# ProPrj___2025-03-14.net
KiCad netlist of a schematic drawn in EasyEDA Pro
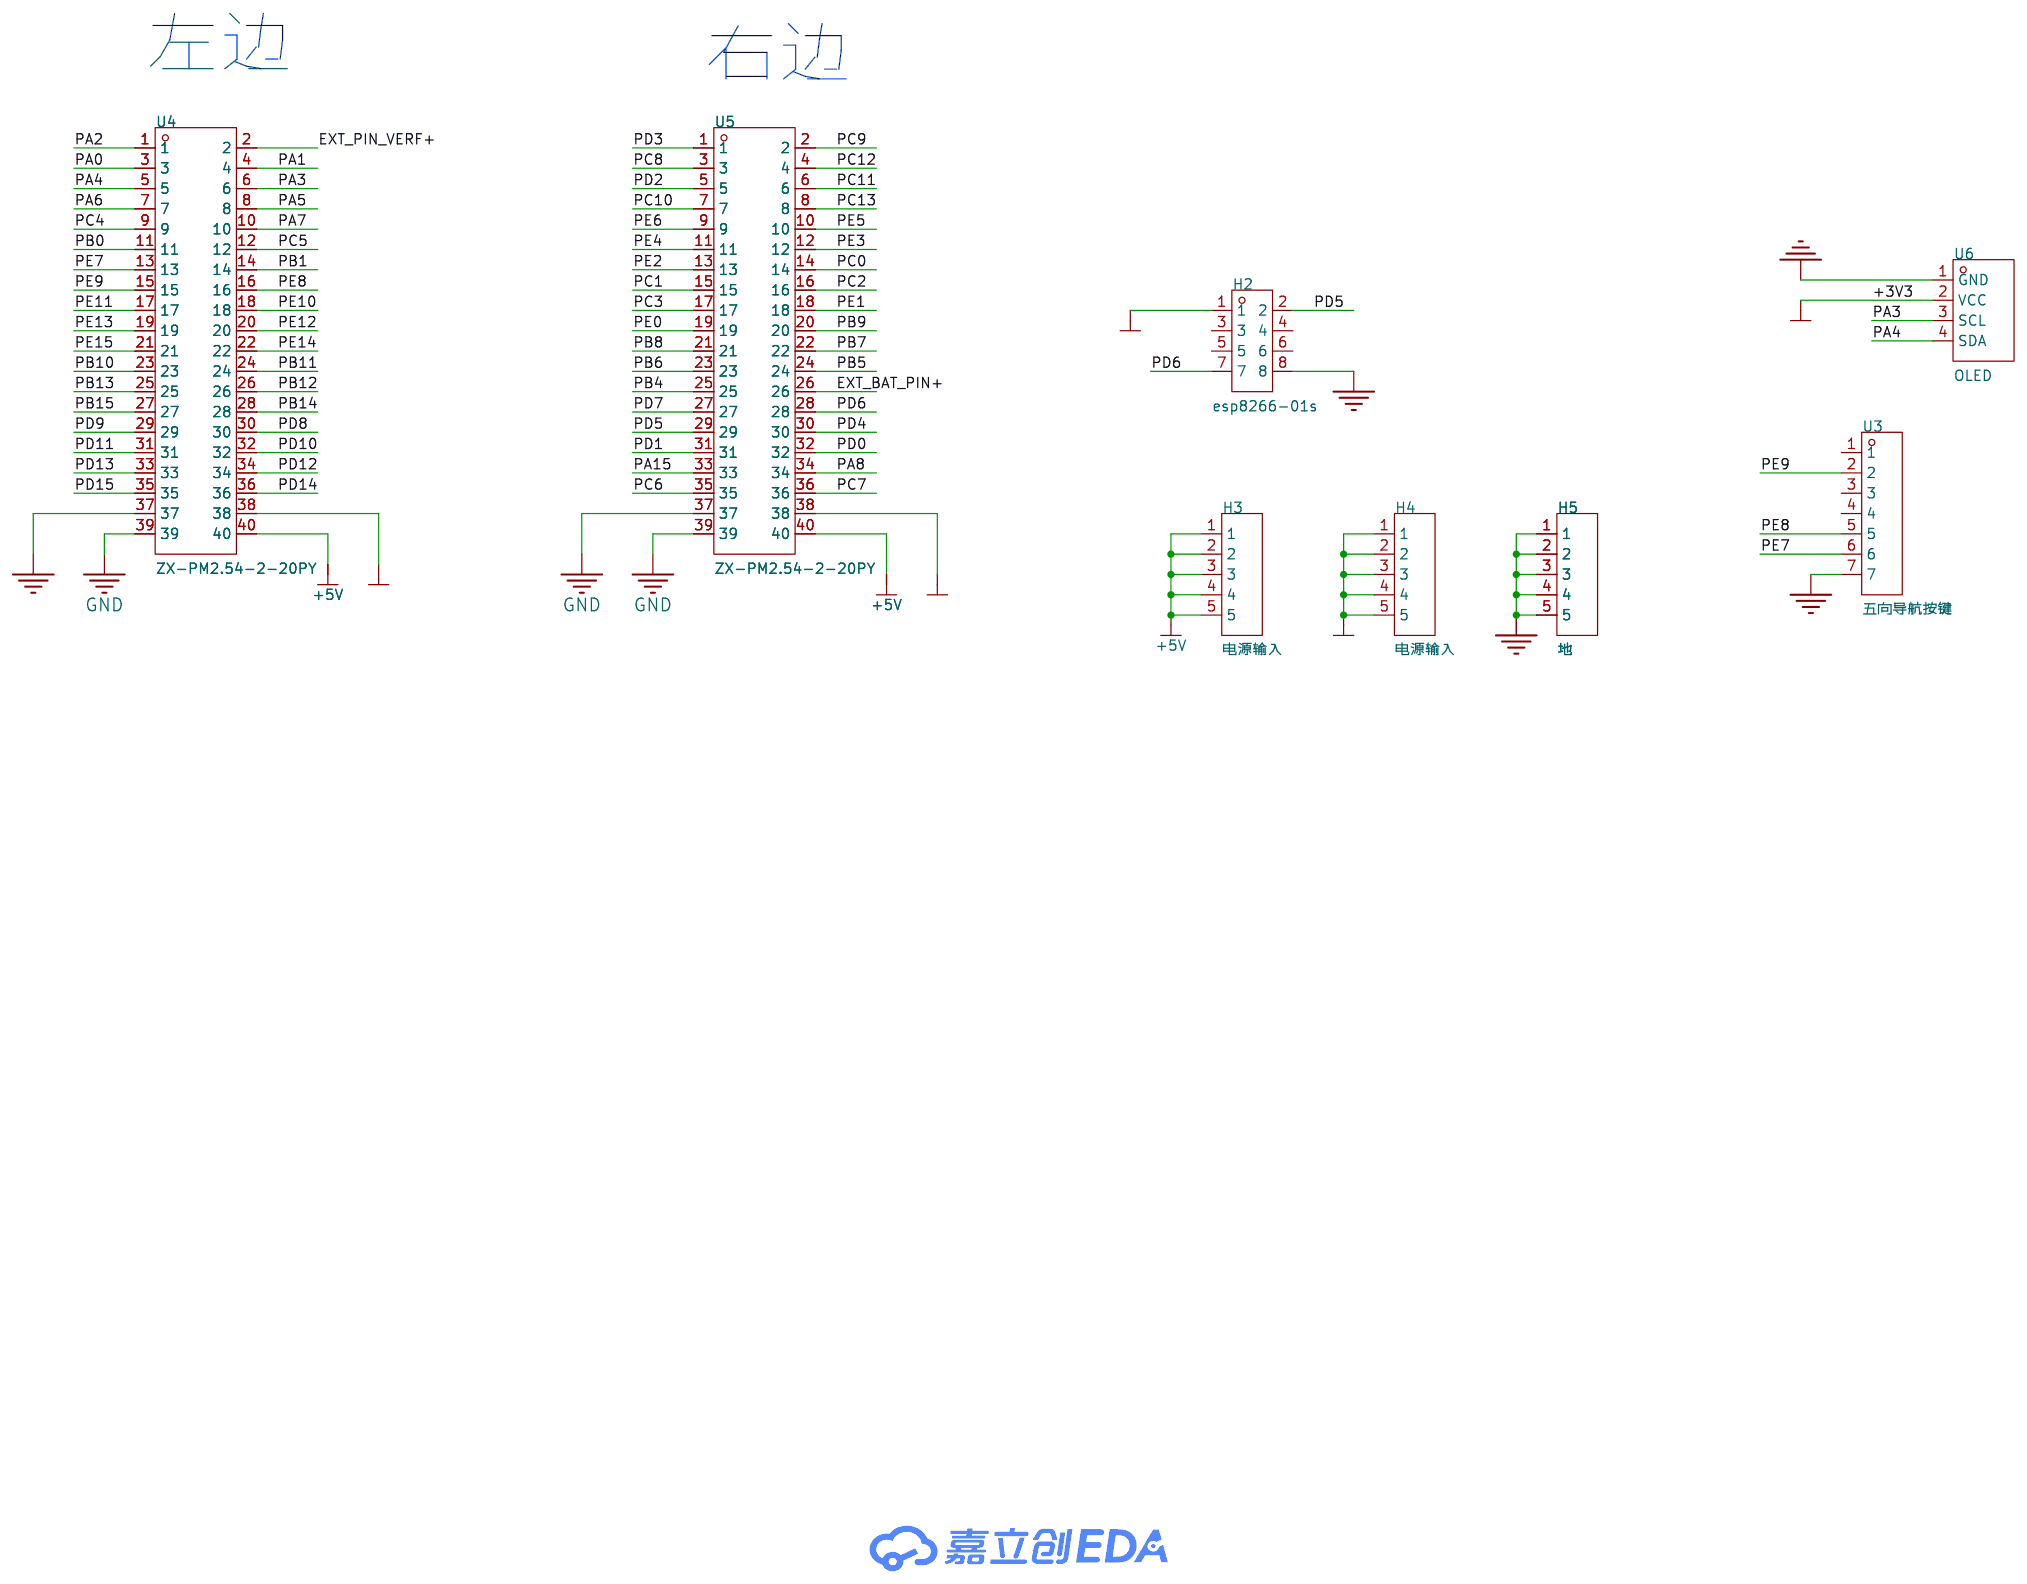
[diagram p0: schematic sheet]

(export (version "E")
  (design (tool "Eeschema 10.0.6"))
  (components
    (comp (ref "H2")
      (value "esp8266-01s")
      (footprint "easyedapro:HDR-TH_8P-P2.54-V-F-R2-C4-S2.54")
      (fields (field (name "Manufacturer Part") "PM254V-12-08-H85") (field (name "Manufacturer") "XFCN(兴飞)"))
      (libsource (lib "easyedapro") (part "PM254V-12-08-H85_C2834799"))
    )
    (comp (ref "H3")
      (value "电源输入")
      (footprint "easyedapro:HDR-TH_5P-P2.54-V-M")
      (fields (field (name "Manufacturer Part") "PZ254V-11-05P") (field (name "Manufacturer") "XFCN(兴飞)"))
      (libsource (lib "easyedapro") (part "PZ254V-11-05P"))
    )
    (comp (ref "H4")
      (value "电源输入")
      (footprint "easyedapro:HDR-TH_5P-P2.54-V-M")
      (fields (field (name "Manufacturer Part") "PZ254V-11-05P") (field (name "Manufacturer") "XFCN(兴飞)"))
      (libsource (lib "easyedapro") (part "PZ254V-11-05P"))
    )
    (comp (ref "H5")
      (value "地")
      (footprint "easyedapro:HDR-TH_5P-P2.54-V-M")
      (fields (field (name "Manufacturer Part") "PZ254V-11-05P") (field (name "Manufacturer") "XFCN(兴飞)"))
      (libsource (lib "easyedapro") (part "PZ254V-11-05P"))
    )
    (comp (ref "U3")
      (value "五向导航按键")
      (footprint "easyedapro:HDR-TH_7P-P2.54-H-F-W10.0-N")
      (fields
        (field (name "Manufacturer Part") "PM254-1-07-W-8.5")
        (field (name "Manufacturer") "HCTL(华灿天禄)")
      )
      (libsource (lib "easyedapro") (part "PM254-1-07-W-8.5"))
    )
    (comp (ref "U4")
      (value "ZX-PM2.54-2-20PY")
      (footprint "easyedapro:HDR-TH_40P-P2.54-V-F-R2-C20-S2.54")
      (fields (field (name "Manufacturer") "Megastar(兆星)"))
      (libsource (lib "easyedapro") (part "ZX-PM2.54-2-20PY"))
    )
    (comp (ref "U5")
      (value "ZX-PM2.54-2-20PY")
      (footprint "easyedapro:HDR-TH_40P-P2.54-V-F-R2-C20-S2.54")
      (fields (field (name "Manufacturer") "Megastar(兆星)"))
      (libsource (lib "easyedapro") (part "ZX-PM2.54-2-20PY"))
    )
    (comp (ref "U6")
      (value "OLED")
      (footprint "easyedapro:OLED-TH_L27.8-W27.2-P2.54_C9900033791")
      (description "主控芯片:SSD1315;接口类型:I2C;尺寸(inch):0.96;像素分辨率:128x64;")
      (fields (field (name "Manufacturer Part") "HS96L03W2C03") (field (name "Manufacturer") "HS(汉昇)"))
      (libsource (lib "easyedapro") (part "HS96L03W2C03"))
    )
  )
  (nets
    (net (code "1") (name "+3V3") (class "Default")
      (node (ref "H2") (pin "1") (pinfunction "1_1") (pintype "unspecified"))
      (node (ref "H4") (pin "1") (pinfunction "1_1") (pintype "unspecified"))
      (node (ref "H4") (pin "2") (pinfunction "2_2") (pintype "unspecified"))
      (node (ref "H4") (pin "3") (pinfunction "3_3") (pintype "unspecified"))
      (node (ref "H4") (pin "4") (pinfunction "4_4") (pintype "unspecified"))
      (node (ref "H4") (pin "5") (pinfunction "5_5") (pintype "unspecified"))
      (node (ref "U4") (pin "38") (pinfunction "38_38") (pintype "unspecified"))
      (node (ref "U5") (pin "38") (pinfunction "38_38") (pintype "unspecified"))
      (node (ref "U6") (pin "2") (pinfunction "VCC_2") (pintype "unspecified"))
    )
    (net (code "2") (name "+5V") (class "Default")
      (node (ref "H3") (pin "1") (pinfunction "1_1") (pintype "unspecified"))
      (node (ref "H3") (pin "2") (pinfunction "2_2") (pintype "unspecified"))
      (node (ref "H3") (pin "3") (pinfunction "3_3") (pintype "unspecified"))
      (node (ref "H3") (pin "4") (pinfunction "4_4") (pintype "unspecified"))
      (node (ref "H3") (pin "5") (pinfunction "5_5") (pintype "unspecified"))
      (node (ref "U4") (pin "40") (pinfunction "40_40") (pintype "unspecified"))
      (node (ref "U5") (pin "40") (pinfunction "40_40") (pintype "unspecified"))
    )
    (net (code "3") (name "/EXT_BAT_PIN+") (class "Default")
      (node (ref "U5") (pin "26") (pinfunction "26_26") (pintype "unspecified"))
    )
    (net (code "4") (name "/EXT_PIN_VERF+") (class "Default")
      (node (ref "U4") (pin "2") (pinfunction "2_2") (pintype "unspecified"))
    )
    (net (code "5") (name "/PA0") (class "Default")
      (node (ref "U4") (pin "3") (pinfunction "3_3") (pintype "unspecified"))
    )
    (net (code "6") (name "/PA1") (class "Default")
      (node (ref "U4") (pin "4") (pinfunction "4_4") (pintype "unspecified"))
    )
    (net (code "7") (name "/PA2") (class "Default")
      (node (ref "U4") (pin "1") (pinfunction "1_1") (pintype "unspecified"))
    )
    (net (code "8") (name "/PA3") (class "Default")
      (node (ref "U4") (pin "6") (pinfunction "6_6") (pintype "unspecified"))
      (node (ref "U6") (pin "3") (pinfunction "SCL_3") (pintype "unspecified"))
    )
    (net (code "9") (name "/PA4") (class "Default")
      (node (ref "U4") (pin "5") (pinfunction "5_5") (pintype "unspecified"))
      (node (ref "U6") (pin "4") (pinfunction "SDA_4") (pintype "unspecified"))
    )
    (net (code "10") (name "/PA5") (class "Default")
      (node (ref "U4") (pin "8") (pinfunction "8_8") (pintype "unspecified"))
    )
    (net (code "11") (name "/PA6") (class "Default")
      (node (ref "U4") (pin "7") (pinfunction "7_7") (pintype "unspecified"))
    )
    (net (code "12") (name "/PA7") (class "Default")
      (node (ref "U4") (pin "10") (pinfunction "10_10") (pintype "unspecified"))
    )
    (net (code "13") (name "/PA8") (class "Default")
      (node (ref "U5") (pin "34") (pinfunction "34_34") (pintype "unspecified"))
    )
    (net (code "14") (name "/PA15") (class "Default")
      (node (ref "U5") (pin "33") (pinfunction "33_33") (pintype "unspecified"))
    )
    (net (code "15") (name "/PB0") (class "Default")
      (node (ref "U4") (pin "11") (pinfunction "11_11") (pintype "unspecified"))
    )
    (net (code "16") (name "/PB1") (class "Default")
      (node (ref "U4") (pin "14") (pinfunction "14_14") (pintype "unspecified"))
    )
    (net (code "17") (name "/PB4") (class "Default")
      (node (ref "U5") (pin "25") (pinfunction "25_25") (pintype "unspecified"))
    )
    (net (code "18") (name "/PB5") (class "Default")
      (node (ref "U5") (pin "24") (pinfunction "24_24") (pintype "unspecified"))
    )
    (net (code "19") (name "/PB6") (class "Default")
      (node (ref "U5") (pin "23") (pinfunction "23_23") (pintype "unspecified"))
    )
    (net (code "20") (name "/PB7") (class "Default")
      (node (ref "U5") (pin "22") (pinfunction "22_22") (pintype "unspecified"))
    )
    (net (code "21") (name "/PB8") (class "Default")
      (node (ref "U5") (pin "21") (pinfunction "21_21") (pintype "unspecified"))
    )
    (net (code "22") (name "/PB9") (class "Default")
      (node (ref "U5") (pin "20") (pinfunction "20_20") (pintype "unspecified"))
    )
    (net (code "23") (name "/PB10") (class "Default")
      (node (ref "U4") (pin "23") (pinfunction "23_23") (pintype "unspecified"))
    )
    (net (code "24") (name "/PB11") (class "Default")
      (node (ref "U4") (pin "24") (pinfunction "24_24") (pintype "unspecified"))
    )
    (net (code "25") (name "/PB12") (class "Default")
      (node (ref "U4") (pin "26") (pinfunction "26_26") (pintype "unspecified"))
    )
    (net (code "26") (name "/PB13") (class "Default")
      (node (ref "U4") (pin "25") (pinfunction "25_25") (pintype "unspecified"))
    )
    (net (code "27") (name "/PB14") (class "Default")
      (node (ref "U4") (pin "28") (pinfunction "28_28") (pintype "unspecified"))
    )
    (net (code "28") (name "/PB15") (class "Default")
      (node (ref "U4") (pin "27") (pinfunction "27_27") (pintype "unspecified"))
    )
    (net (code "29") (name "/PC0") (class "Default")
      (node (ref "U5") (pin "14") (pinfunction "14_14") (pintype "unspecified"))
    )
    (net (code "30") (name "/PC1") (class "Default")
      (node (ref "U5") (pin "15") (pinfunction "15_15") (pintype "unspecified"))
    )
    (net (code "31") (name "/PC2") (class "Default")
      (node (ref "U5") (pin "16") (pinfunction "16_16") (pintype "unspecified"))
    )
    (net (code "32") (name "/PC3") (class "Default")
      (node (ref "U5") (pin "17") (pinfunction "17_17") (pintype "unspecified"))
    )
    (net (code "33") (name "/PC4") (class "Default")
      (node (ref "U4") (pin "9") (pinfunction "9_9") (pintype "unspecified"))
    )
    (net (code "34") (name "/PC5") (class "Default")
      (node (ref "U4") (pin "12") (pinfunction "12_12") (pintype "unspecified"))
    )
    (net (code "35") (name "/PC6") (class "Default")
      (node (ref "U5") (pin "35") (pinfunction "35_35") (pintype "unspecified"))
    )
    (net (code "36") (name "/PC7") (class "Default")
      (node (ref "U5") (pin "36") (pinfunction "36_36") (pintype "unspecified"))
    )
    (net (code "37") (name "/PC8") (class "Default")
      (node (ref "U5") (pin "3") (pinfunction "3_3") (pintype "unspecified"))
    )
    (net (code "38") (name "/PC9") (class "Default")
      (node (ref "U5") (pin "2") (pinfunction "2_2") (pintype "unspecified"))
    )
    (net (code "39") (name "/PC10") (class "Default")
      (node (ref "U5") (pin "7") (pinfunction "7_7") (pintype "unspecified"))
    )
    (net (code "40") (name "/PC11") (class "Default")
      (node (ref "U5") (pin "6") (pinfunction "6_6") (pintype "unspecified"))
    )
    (net (code "41") (name "/PC12") (class "Default")
      (node (ref "U5") (pin "4") (pinfunction "4_4") (pintype "unspecified"))
    )
    (net (code "42") (name "/PC13") (class "Default")
      (node (ref "U5") (pin "8") (pinfunction "8_8") (pintype "unspecified"))
    )
    (net (code "43") (name "/PD0") (class "Default")
      (node (ref "U5") (pin "32") (pinfunction "32_32") (pintype "unspecified"))
    )
    (net (code "44") (name "/PD1") (class "Default")
      (node (ref "U5") (pin "31") (pinfunction "31_31") (pintype "unspecified"))
    )
    (net (code "45") (name "/PD2") (class "Default")
      (node (ref "U5") (pin "5") (pinfunction "5_5") (pintype "unspecified"))
    )
    (net (code "46") (name "/PD3") (class "Default")
      (node (ref "U5") (pin "1") (pinfunction "1_1") (pintype "unspecified"))
    )
    (net (code "47") (name "/PD4") (class "Default")
      (node (ref "U5") (pin "30") (pinfunction "30_30") (pintype "unspecified"))
    )
    (net (code "48") (name "/PD5") (class "Default")
      (node (ref "H2") (pin "2") (pinfunction "2_2") (pintype "unspecified"))
      (node (ref "U5") (pin "29") (pinfunction "29_29") (pintype "unspecified"))
    )
    (net (code "49") (name "/PD6") (class "Default")
      (node (ref "H2") (pin "7") (pinfunction "7_7") (pintype "unspecified"))
      (node (ref "U5") (pin "28") (pinfunction "28_28") (pintype "unspecified"))
    )
    (net (code "50") (name "/PD7") (class "Default")
      (node (ref "U5") (pin "27") (pinfunction "27_27") (pintype "unspecified"))
    )
    (net (code "51") (name "/PD8") (class "Default")
      (node (ref "U4") (pin "30") (pinfunction "30_30") (pintype "unspecified"))
    )
    (net (code "52") (name "/PD9") (class "Default")
      (node (ref "U4") (pin "29") (pinfunction "29_29") (pintype "unspecified"))
    )
    (net (code "53") (name "/PD10") (class "Default")
      (node (ref "U4") (pin "32") (pinfunction "32_32") (pintype "unspecified"))
    )
    (net (code "54") (name "/PD11") (class "Default")
      (node (ref "U4") (pin "31") (pinfunction "31_31") (pintype "unspecified"))
    )
    (net (code "55") (name "/PD12") (class "Default")
      (node (ref "U4") (pin "34") (pinfunction "34_34") (pintype "unspecified"))
    )
    (net (code "56") (name "/PD13") (class "Default")
      (node (ref "U4") (pin "33") (pinfunction "33_33") (pintype "unspecified"))
    )
    (net (code "57") (name "/PD14") (class "Default")
      (node (ref "U4") (pin "36") (pinfunction "36_36") (pintype "unspecified"))
    )
    (net (code "58") (name "/PD15") (class "Default")
      (node (ref "U4") (pin "35") (pinfunction "35_35") (pintype "unspecified"))
    )
    (net (code "59") (name "/PE0") (class "Default")
      (node (ref "U5") (pin "19") (pinfunction "19_19") (pintype "unspecified"))
    )
    (net (code "60") (name "/PE1") (class "Default")
      (node (ref "U5") (pin "18") (pinfunction "18_18") (pintype "unspecified"))
    )
    (net (code "61") (name "/PE2") (class "Default")
      (node (ref "U5") (pin "13") (pinfunction "13_13") (pintype "unspecified"))
    )
    (net (code "62") (name "/PE3") (class "Default")
      (node (ref "U5") (pin "12") (pinfunction "12_12") (pintype "unspecified"))
    )
    (net (code "63") (name "/PE4") (class "Default")
      (node (ref "U5") (pin "11") (pinfunction "11_11") (pintype "unspecified"))
    )
    (net (code "64") (name "/PE5") (class "Default")
      (node (ref "U5") (pin "10") (pinfunction "10_10") (pintype "unspecified"))
    )
    (net (code "65") (name "/PE6") (class "Default")
      (node (ref "U5") (pin "9") (pinfunction "9_9") (pintype "unspecified"))
    )
    (net (code "66") (name "/PE7") (class "Default")
      (node (ref "U3") (pin "6") (pinfunction "6_6") (pintype "unspecified"))
      (node (ref "U4") (pin "13") (pinfunction "13_13") (pintype "unspecified"))
    )
    (net (code "67") (name "/PE8") (class "Default")
      (node (ref "U3") (pin "5") (pinfunction "5_5") (pintype "unspecified"))
      (node (ref "U4") (pin "16") (pinfunction "16_16") (pintype "unspecified"))
    )
    (net (code "68") (name "/PE9") (class "Default")
      (node (ref "U3") (pin "2") (pinfunction "2_2") (pintype "unspecified"))
      (node (ref "U4") (pin "15") (pinfunction "15_15") (pintype "unspecified"))
    )
    (net (code "69") (name "/PE10") (class "Default")
      (node (ref "U4") (pin "18") (pinfunction "18_18") (pintype "unspecified"))
    )
    (net (code "70") (name "/PE11") (class "Default")
      (node (ref "U4") (pin "17") (pinfunction "17_17") (pintype "unspecified"))
    )
    (net (code "71") (name "/PE12") (class "Default")
      (node (ref "U4") (pin "20") (pinfunction "20_20") (pintype "unspecified"))
    )
    (net (code "72") (name "/PE13") (class "Default")
      (node (ref "U4") (pin "19") (pinfunction "19_19") (pintype "unspecified"))
    )
    (net (code "73") (name "/PE14") (class "Default")
      (node (ref "U4") (pin "22") (pinfunction "22_22") (pintype "unspecified"))
    )
    (net (code "74") (name "/PE15") (class "Default")
      (node (ref "U4") (pin "21") (pinfunction "21_21") (pintype "unspecified"))
    )
    (net (code "75") (name "AGND") (class "Default")
      (node (ref "U4") (pin "37") (pinfunction "37_37") (pintype "unspecified"))
    )
    (net (code "76") (name "GND") (class "Default")
      (node (ref "H2") (pin "8") (pinfunction "8_8") (pintype "unspecified"))
      (node (ref "H5") (pin "1") (pinfunction "1_1") (pintype "unspecified"))
      (node (ref "H5") (pin "2") (pinfunction "2_2") (pintype "unspecified"))
      (node (ref "H5") (pin "3") (pinfunction "3_3") (pintype "unspecified"))
      (node (ref "H5") (pin "4") (pinfunction "4_4") (pintype "unspecified"))
      (node (ref "H5") (pin "5") (pinfunction "5_5") (pintype "unspecified"))
      (node (ref "U3") (pin "7") (pinfunction "7_7") (pintype "unspecified"))
      (node (ref "U4") (pin "39") (pinfunction "39_39") (pintype "unspecified"))
      (node (ref "U5") (pin "37") (pinfunction "37_37") (pintype "unspecified"))
      (node (ref "U5") (pin "39") (pinfunction "39_39") (pintype "unspecified"))
      (node (ref "U6") (pin "1") (pinfunction "GND_1") (pintype "unspecified"))
    )
    (net (code "77") (name "unconnected-(H2-Pad3)") (class "Default")
      (node (ref "H2") (pin "3") (pinfunction "3_3") (pintype "unspecified"))
    )
    (net (code "78") (name "unconnected-(H2-Pad4)") (class "Default")
      (node (ref "H2") (pin "4") (pinfunction "4_4") (pintype "unspecified"))
    )
    (net (code "79") (name "unconnected-(H2-Pad5)") (class "Default")
      (node (ref "H2") (pin "5") (pinfunction "5_5") (pintype "unspecified"))
    )
    (net (code "80") (name "unconnected-(H2-Pad6)") (class "Default")
      (node (ref "H2") (pin "6") (pinfunction "6_6") (pintype "unspecified"))
    )
    (net (code "81") (name "unconnected-(U3-Pad1)") (class "Default")
      (node (ref "U3") (pin "1") (pinfunction "1_1") (pintype "unspecified"))
    )
    (net (code "82") (name "unconnected-(U3-Pad3)") (class "Default")
      (node (ref "U3") (pin "3") (pinfunction "3_3") (pintype "unspecified"))
    )
    (net (code "83") (name "unconnected-(U3-Pad4)") (class "Default")
      (node (ref "U3") (pin "4") (pinfunction "4_4") (pintype "unspecified"))
    )
  )
)
